# FPGA_IO.net
KiCad netlist of a schematic drawn in Altium Designer
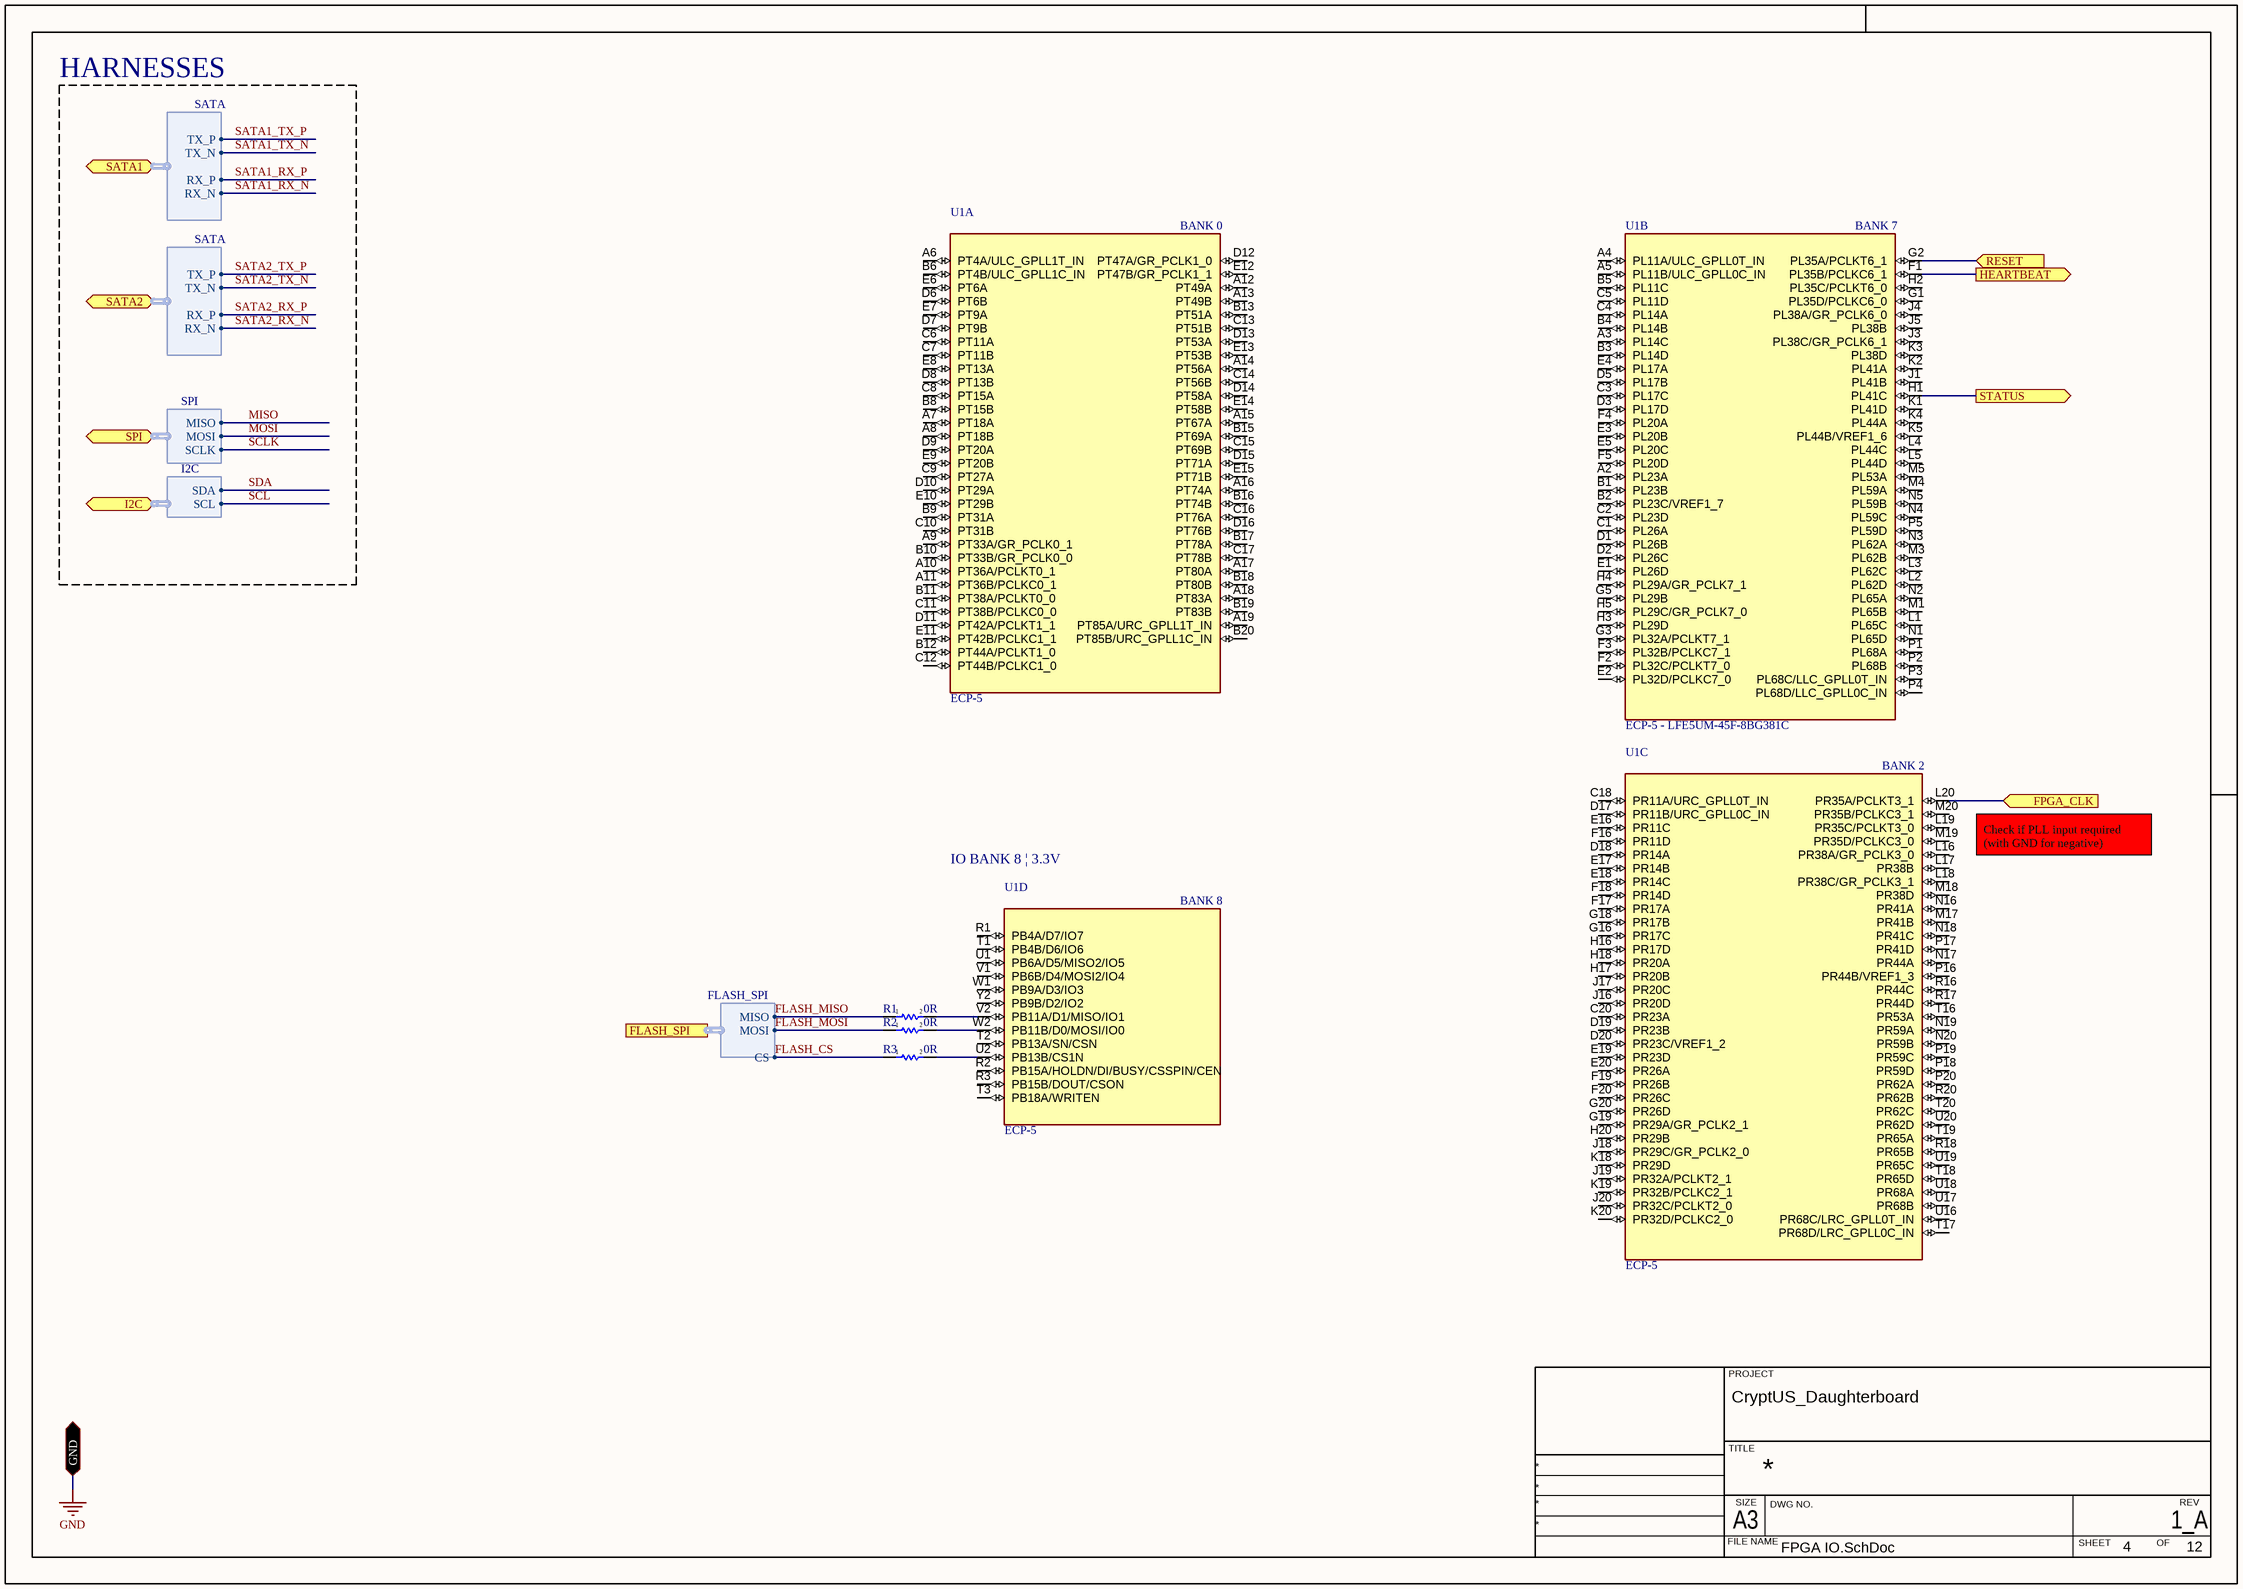
[diagram p0: FPGA IO.SchDoc]

(export (version "E")
  (design (tool "Eeschema 10.0.6"))
  (components
    (comp (ref "R1")
      (value "0R")
      (footprint "RES_0603")
      (description "Resistor")
      (fields (field (name "POWER") "1/8W") (field (name "TOLERANCE") "10%"))
      (libsource (lib "Symbols") (part "RESISTOR"))
    )
    (comp (ref "R2")
      (value "0R")
      (footprint "RES_0603")
      (description "Resistor")
      (fields (field (name "POWER") "1/8W") (field (name "TOLERANCE") "10%"))
      (libsource (lib "Symbols") (part "RESISTOR"))
    )
    (comp (ref "R3")
      (value "0R")
      (footprint "RES_0603")
      (description "Resistor")
      (fields (field (name "POWER") "1/8W") (field (name "TOLERANCE") "10%"))
      (libsource (lib "Symbols") (part "RESISTOR"))
    )
    (comp (ref "U1")
      (value "ECP-5")
      (footprint "CryptLib:CABGA-381")
      (description "IC FPGA 203 I/O 381CABGA")
      (fields (field (name "MFR") "Lattice Semiconductors"))
      (libsource (lib "CryptLib") (part "IC_LFE5UM-45F-8BG381C"))
    )
  )
  (nets
    (net (code "5") (name "/FLASH_CS") (class "Default")
      (node (ref "R3") (pin "1") (pinfunction "1_1") (pintype "passive"))
    )
    (net (code "6") (name "/FLASH_MISO") (class "Default")
      (node (ref "R1") (pin "1") (pinfunction "1_1") (pintype "passive"))
    )
    (net (code "7") (name "/FLASH_MOSI") (class "Default")
      (node (ref "R2") (pin "1") (pinfunction "1_1") (pintype "passive"))
    )
    (net (code "8") (name "/FPGA_CLK") (class "Default")
      (node (ref "U1") (pin "L20") (pinfunction "PR35A/PCLKT3_1_L20") (pintype "bidirectional"))
    )
    (net (code "9") (name "/HEARTBEAT") (class "Default")
      (node (ref "U1") (pin "F1") (pinfunction "PL35B/PCLKC6_1_F1") (pintype "bidirectional"))
    )
    (net (code "12") (name "/RESET") (class "Default")
      (node (ref "U1") (pin "G2") (pinfunction "PL35A/PCLKT6_1_G2") (pintype "bidirectional"))
    )
    (net (code "24") (name "/STATUS") (class "Default")
      (node (ref "U1") (pin "H1") (pinfunction "PL41C_H1") (pintype "bidirectional"))
    )
    (net (code "30") (name "Net-(U1D-PB11A{slash}D1{slash}MISO{slash}IO1)") (class "Default")
      (node (ref "R1") (pin "2") (pinfunction "2_2") (pintype "passive"))
      (node (ref "U1") (pin "V2") (pinfunction "PB11A/D1/MISO/IO1_V2") (pintype "bidirectional"))
    )
    (net (code "31") (name "Net-(U1D-PB11B{slash}D0{slash}MOSI{slash}IO0)") (class "Default")
      (node (ref "R2") (pin "2") (pinfunction "2_2") (pintype "passive"))
      (node (ref "U1") (pin "W2") (pinfunction "PB11B/D0/MOSI/IO0_W2") (pintype "bidirectional"))
    )
    (net (code "32") (name "Net-(U1D-PB13B{slash}CS1N)") (class "Default")
      (node (ref "R3") (pin "2") (pinfunction "2_2") (pintype "passive"))
      (node (ref "U1") (pin "U2") (pinfunction "PB13B/CS1N_U2") (pintype "bidirectional"))
    )
    (net (code "33") (name "unconnected-(U1A-PT4A{slash}ULC_GPLL1T_IN-PadA6)") (class "Default")
      (node (ref "U1") (pin "A6") (pinfunction "PT4A/ULC_GPLL1T_IN_A6") (pintype "bidirectional"))
    )
    (net (code "34") (name "unconnected-(U1A-PT4B{slash}ULC_GPLL1C_IN-PadB6)") (class "Default")
      (node (ref "U1") (pin "B6") (pinfunction "PT4B/ULC_GPLL1C_IN_B6") (pintype "bidirectional"))
    )
    (net (code "35") (name "unconnected-(U1A-PT6A-PadE6)") (class "Default")
      (node (ref "U1") (pin "E6") (pinfunction "PT6A_E6") (pintype "bidirectional"))
    )
    (net (code "36") (name "unconnected-(U1A-PT6B-PadD6)") (class "Default")
      (node (ref "U1") (pin "D6") (pinfunction "PT6B_D6") (pintype "bidirectional"))
    )
    (net (code "37") (name "unconnected-(U1A-PT9A-PadE7)") (class "Default")
      (node (ref "U1") (pin "E7") (pinfunction "PT9A_E7") (pintype "bidirectional"))
    )
    (net (code "38") (name "unconnected-(U1A-PT9B-PadD7)") (class "Default")
      (node (ref "U1") (pin "D7") (pinfunction "PT9B_D7") (pintype "bidirectional"))
    )
    (net (code "39") (name "unconnected-(U1A-PT11A-PadC6)") (class "Default")
      (node (ref "U1") (pin "C6") (pinfunction "PT11A_C6") (pintype "bidirectional"))
    )
    (net (code "40") (name "unconnected-(U1A-PT11B-PadC7)") (class "Default")
      (node (ref "U1") (pin "C7") (pinfunction "PT11B_C7") (pintype "bidirectional"))
    )
    (net (code "41") (name "unconnected-(U1A-PT13A-PadE8)") (class "Default")
      (node (ref "U1") (pin "E8") (pinfunction "PT13A_E8") (pintype "bidirectional"))
    )
    (net (code "42") (name "unconnected-(U1A-PT13B-PadD8)") (class "Default")
      (node (ref "U1") (pin "D8") (pinfunction "PT13B_D8") (pintype "bidirectional"))
    )
    (net (code "43") (name "unconnected-(U1A-PT15A-PadC8)") (class "Default")
      (node (ref "U1") (pin "C8") (pinfunction "PT15A_C8") (pintype "bidirectional"))
    )
    (net (code "44") (name "unconnected-(U1A-PT15B-PadB8)") (class "Default")
      (node (ref "U1") (pin "B8") (pinfunction "PT15B_B8") (pintype "bidirectional"))
    )
    (net (code "45") (name "unconnected-(U1A-PT18A-PadA7)") (class "Default")
      (node (ref "U1") (pin "A7") (pinfunction "PT18A_A7") (pintype "bidirectional"))
    )
    (net (code "46") (name "unconnected-(U1A-PT18B-PadA8)") (class "Default")
      (node (ref "U1") (pin "A8") (pinfunction "PT18B_A8") (pintype "bidirectional"))
    )
    (net (code "47") (name "unconnected-(U1A-PT20A-PadD9)") (class "Default")
      (node (ref "U1") (pin "D9") (pinfunction "PT20A_D9") (pintype "bidirectional"))
    )
    (net (code "48") (name "unconnected-(U1A-PT20B-PadE9)") (class "Default")
      (node (ref "U1") (pin "E9") (pinfunction "PT20B_E9") (pintype "bidirectional"))
    )
    (net (code "49") (name "unconnected-(U1A-PT27A-PadC9)") (class "Default")
      (node (ref "U1") (pin "C9") (pinfunction "PT27A_C9") (pintype "bidirectional"))
    )
    (net (code "50") (name "unconnected-(U1A-PT29A-PadD10)") (class "Default")
      (node (ref "U1") (pin "D10") (pinfunction "PT29A_D10") (pintype "bidirectional"))
    )
    (net (code "51") (name "unconnected-(U1A-PT29B-PadE10)") (class "Default")
      (node (ref "U1") (pin "E10") (pinfunction "PT29B_E10") (pintype "bidirectional"))
    )
    (net (code "52") (name "unconnected-(U1A-PT31A-PadB9)") (class "Default")
      (node (ref "U1") (pin "B9") (pinfunction "PT31A_B9") (pintype "bidirectional"))
    )
    (net (code "53") (name "unconnected-(U1A-PT31B-PadC10)") (class "Default")
      (node (ref "U1") (pin "C10") (pinfunction "PT31B_C10") (pintype "bidirectional"))
    )
    (net (code "54") (name "unconnected-(U1A-PT33A{slash}GR_PCLK0_1-PadA9)") (class "Default")
      (node (ref "U1") (pin "A9") (pinfunction "PT33A/GR_PCLK0_1_A9") (pintype "bidirectional"))
    )
    (net (code "55") (name "unconnected-(U1A-PT33B{slash}GR_PCLK0_0-PadB10)") (class "Default")
      (node (ref "U1") (pin "B10") (pinfunction "PT33B/GR_PCLK0_0_B10") (pintype "bidirectional"))
    )
    (net (code "56") (name "unconnected-(U1A-PT36A{slash}PCLKT0_1-PadA10)") (class "Default")
      (node (ref "U1") (pin "A10") (pinfunction "PT36A/PCLKT0_1_A10") (pintype "bidirectional"))
    )
    (net (code "57") (name "unconnected-(U1A-PT36B{slash}PCLKC0_1-PadA11)") (class "Default")
      (node (ref "U1") (pin "A11") (pinfunction "PT36B/PCLKC0_1_A11") (pintype "bidirectional"))
    )
    (net (code "58") (name "unconnected-(U1A-PT38A{slash}PCLKT0_0-PadB11)") (class "Default")
      (node (ref "U1") (pin "B11") (pinfunction "PT38A/PCLKT0_0_B11") (pintype "bidirectional"))
    )
    (net (code "59") (name "unconnected-(U1A-PT38B{slash}PCLKC0_0-PadC11)") (class "Default")
      (node (ref "U1") (pin "C11") (pinfunction "PT38B/PCLKC0_0_C11") (pintype "bidirectional"))
    )
    (net (code "60") (name "unconnected-(U1A-PT42A{slash}PCLKT1_1-PadD11)") (class "Default")
      (node (ref "U1") (pin "D11") (pinfunction "PT42A/PCLKT1_1_D11") (pintype "bidirectional"))
    )
    (net (code "61") (name "unconnected-(U1A-PT42B{slash}PCLKC1_1-PadE11)") (class "Default")
      (node (ref "U1") (pin "E11") (pinfunction "PT42B/PCLKC1_1_E11") (pintype "bidirectional"))
    )
    (net (code "62") (name "unconnected-(U1A-PT44A{slash}PCLKT1_0-PadB12)") (class "Default")
      (node (ref "U1") (pin "B12") (pinfunction "PT44A/PCLKT1_0_B12") (pintype "bidirectional"))
    )
    (net (code "63") (name "unconnected-(U1A-PT44B{slash}PCLKC1_0-PadC12)") (class "Default")
      (node (ref "U1") (pin "C12") (pinfunction "PT44B/PCLKC1_0_C12") (pintype "bidirectional"))
    )
    (net (code "64") (name "unconnected-(U1A-PT47A{slash}GR_PCLK1_0-PadD12)") (class "Default")
      (node (ref "U1") (pin "D12") (pinfunction "PT47A/GR_PCLK1_0_D12") (pintype "bidirectional"))
    )
    (net (code "65") (name "unconnected-(U1A-PT47B{slash}GR_PCLK1_1-PadE12)") (class "Default")
      (node (ref "U1") (pin "E12") (pinfunction "PT47B/GR_PCLK1_1_E12") (pintype "bidirectional"))
    )
    (net (code "66") (name "unconnected-(U1A-PT49A-PadA12)") (class "Default")
      (node (ref "U1") (pin "A12") (pinfunction "PT49A_A12") (pintype "bidirectional"))
    )
    (net (code "67") (name "unconnected-(U1A-PT49B-PadA13)") (class "Default")
      (node (ref "U1") (pin "A13") (pinfunction "PT49B_A13") (pintype "bidirectional"))
    )
    (net (code "68") (name "unconnected-(U1A-PT51A-PadB13)") (class "Default")
      (node (ref "U1") (pin "B13") (pinfunction "PT51A_B13") (pintype "bidirectional"))
    )
    (net (code "69") (name "unconnected-(U1A-PT51B-PadC13)") (class "Default")
      (node (ref "U1") (pin "C13") (pinfunction "PT51B_C13") (pintype "bidirectional"))
    )
    (net (code "70") (name "unconnected-(U1A-PT53A-PadD13)") (class "Default")
      (node (ref "U1") (pin "D13") (pinfunction "PT53A_D13") (pintype "bidirectional"))
    )
    (net (code "71") (name "unconnected-(U1A-PT53B-PadE13)") (class "Default")
      (node (ref "U1") (pin "E13") (pinfunction "PT53B_E13") (pintype "bidirectional"))
    )
    (net (code "72") (name "unconnected-(U1A-PT56A-PadA14)") (class "Default")
      (node (ref "U1") (pin "A14") (pinfunction "PT56A_A14") (pintype "bidirectional"))
    )
    (net (code "73") (name "unconnected-(U1A-PT56B-PadC14)") (class "Default")
      (node (ref "U1") (pin "C14") (pinfunction "PT56B_C14") (pintype "bidirectional"))
    )
    (net (code "74") (name "unconnected-(U1A-PT58A-PadD14)") (class "Default")
      (node (ref "U1") (pin "D14") (pinfunction "PT58A_D14") (pintype "bidirectional"))
    )
    (net (code "75") (name "unconnected-(U1A-PT58B-PadE14)") (class "Default")
      (node (ref "U1") (pin "E14") (pinfunction "PT58B_E14") (pintype "bidirectional"))
    )
    (net (code "76") (name "unconnected-(U1A-PT67A-PadA15)") (class "Default")
      (node (ref "U1") (pin "A15") (pinfunction "PT67A_A15") (pintype "bidirectional"))
    )
    (net (code "77") (name "unconnected-(U1A-PT69A-PadB15)") (class "Default")
      (node (ref "U1") (pin "B15") (pinfunction "PT69A_B15") (pintype "bidirectional"))
    )
    (net (code "78") (name "unconnected-(U1A-PT69B-PadC15)") (class "Default")
      (node (ref "U1") (pin "C15") (pinfunction "PT69B_C15") (pintype "bidirectional"))
    )
    (net (code "79") (name "unconnected-(U1A-PT71A-PadD15)") (class "Default")
      (node (ref "U1") (pin "D15") (pinfunction "PT71A_D15") (pintype "bidirectional"))
    )
    (net (code "80") (name "unconnected-(U1A-PT71B-PadE15)") (class "Default")
      (node (ref "U1") (pin "E15") (pinfunction "PT71B_E15") (pintype "bidirectional"))
    )
    (net (code "81") (name "unconnected-(U1A-PT74A-PadA16)") (class "Default")
      (node (ref "U1") (pin "A16") (pinfunction "PT74A_A16") (pintype "bidirectional"))
    )
    (net (code "82") (name "unconnected-(U1A-PT74B-PadB16)") (class "Default")
      (node (ref "U1") (pin "B16") (pinfunction "PT74B_B16") (pintype "bidirectional"))
    )
    (net (code "83") (name "unconnected-(U1A-PT76A-PadC16)") (class "Default")
      (node (ref "U1") (pin "C16") (pinfunction "PT76A_C16") (pintype "bidirectional"))
    )
    (net (code "84") (name "unconnected-(U1A-PT76B-PadD16)") (class "Default")
      (node (ref "U1") (pin "D16") (pinfunction "PT76B_D16") (pintype "bidirectional"))
    )
    (net (code "85") (name "unconnected-(U1A-PT78A-PadB17)") (class "Default")
      (node (ref "U1") (pin "B17") (pinfunction "PT78A_B17") (pintype "bidirectional"))
    )
    (net (code "86") (name "unconnected-(U1A-PT78B-PadC17)") (class "Default")
      (node (ref "U1") (pin "C17") (pinfunction "PT78B_C17") (pintype "bidirectional"))
    )
    (net (code "87") (name "unconnected-(U1A-PT80A-PadA17)") (class "Default")
      (node (ref "U1") (pin "A17") (pinfunction "PT80A_A17") (pintype "bidirectional"))
    )
    (net (code "88") (name "unconnected-(U1A-PT80B-PadB18)") (class "Default")
      (node (ref "U1") (pin "B18") (pinfunction "PT80B_B18") (pintype "bidirectional"))
    )
    (net (code "89") (name "unconnected-(U1A-PT83A-PadA18)") (class "Default")
      (node (ref "U1") (pin "A18") (pinfunction "PT83A_A18") (pintype "bidirectional"))
    )
    (net (code "90") (name "unconnected-(U1A-PT83B-PadB19)") (class "Default")
      (node (ref "U1") (pin "B19") (pinfunction "PT83B_B19") (pintype "bidirectional"))
    )
    (net (code "91") (name "unconnected-(U1A-PT85A{slash}URC_GPLL1T_IN-PadA19)") (class "Default")
      (node (ref "U1") (pin "A19") (pinfunction "PT85A/URC_GPLL1T_IN_A19") (pintype "bidirectional"))
    )
    (net (code "92") (name "unconnected-(U1A-PT85B{slash}URC_GPLL1C_IN-PadB20)") (class "Default")
      (node (ref "U1") (pin "B20") (pinfunction "PT85B/URC_GPLL1C_IN_B20") (pintype "bidirectional"))
    )
    (net (code "93") (name "unconnected-(U1B-PL11A{slash}ULC_GPLL0T_IN-PadA4)") (class "Default")
      (node (ref "U1") (pin "A4") (pinfunction "PL11A/ULC_GPLL0T_IN_A4") (pintype "bidirectional"))
    )
    (net (code "94") (name "unconnected-(U1B-PL11B{slash}ULC_GPLL0C_IN-PadA5)") (class "Default")
      (node (ref "U1") (pin "A5") (pinfunction "PL11B/ULC_GPLL0C_IN_A5") (pintype "bidirectional"))
    )
    (net (code "95") (name "unconnected-(U1B-PL11C-PadB5)") (class "Default")
      (node (ref "U1") (pin "B5") (pinfunction "PL11C_B5") (pintype "bidirectional"))
    )
    (net (code "96") (name "unconnected-(U1B-PL11D-PadC5)") (class "Default")
      (node (ref "U1") (pin "C5") (pinfunction "PL11D_C5") (pintype "bidirectional"))
    )
    (net (code "97") (name "unconnected-(U1B-PL14A-PadC4)") (class "Default")
      (node (ref "U1") (pin "C4") (pinfunction "PL14A_C4") (pintype "bidirectional"))
    )
    (net (code "98") (name "unconnected-(U1B-PL14B-PadB4)") (class "Default")
      (node (ref "U1") (pin "B4") (pinfunction "PL14B_B4") (pintype "bidirectional"))
    )
    (net (code "99") (name "unconnected-(U1B-PL14C-PadA3)") (class "Default")
      (node (ref "U1") (pin "A3") (pinfunction "PL14C_A3") (pintype "bidirectional"))
    )
    (net (code "100") (name "unconnected-(U1B-PL14D-PadB3)") (class "Default")
      (node (ref "U1") (pin "B3") (pinfunction "PL14D_B3") (pintype "bidirectional"))
    )
    (net (code "101") (name "unconnected-(U1B-PL17A-PadE4)") (class "Default")
      (node (ref "U1") (pin "E4") (pinfunction "PL17A_E4") (pintype "bidirectional"))
    )
    (net (code "102") (name "unconnected-(U1B-PL17B-PadD5)") (class "Default")
      (node (ref "U1") (pin "D5") (pinfunction "PL17B_D5") (pintype "bidirectional"))
    )
    (net (code "103") (name "unconnected-(U1B-PL17C-PadC3)") (class "Default")
      (node (ref "U1") (pin "C3") (pinfunction "PL17C_C3") (pintype "bidirectional"))
    )
    (net (code "104") (name "unconnected-(U1B-PL17D-PadD3)") (class "Default")
      (node (ref "U1") (pin "D3") (pinfunction "PL17D_D3") (pintype "bidirectional"))
    )
    (net (code "105") (name "unconnected-(U1B-PL20A-PadF4)") (class "Default")
      (node (ref "U1") (pin "F4") (pinfunction "PL20A_F4") (pintype "bidirectional"))
    )
    (net (code "106") (name "unconnected-(U1B-PL20B-PadE3)") (class "Default")
      (node (ref "U1") (pin "E3") (pinfunction "PL20B_E3") (pintype "bidirectional"))
    )
    (net (code "107") (name "unconnected-(U1B-PL20C-PadE5)") (class "Default")
      (node (ref "U1") (pin "E5") (pinfunction "PL20C_E5") (pintype "bidirectional"))
    )
    (net (code "108") (name "unconnected-(U1B-PL20D-PadF5)") (class "Default")
      (node (ref "U1") (pin "F5") (pinfunction "PL20D_F5") (pintype "bidirectional"))
    )
    (net (code "109") (name "unconnected-(U1B-PL23A-PadA2)") (class "Default")
      (node (ref "U1") (pin "A2") (pinfunction "PL23A_A2") (pintype "bidirectional"))
    )
    (net (code "110") (name "unconnected-(U1B-PL23B-PadB1)") (class "Default")
      (node (ref "U1") (pin "B1") (pinfunction "PL23B_B1") (pintype "bidirectional"))
    )
    (net (code "111") (name "unconnected-(U1B-PL23C{slash}VREF1_7-PadB2)") (class "Default")
      (node (ref "U1") (pin "B2") (pinfunction "PL23C/VREF1_7_B2") (pintype "bidirectional"))
    )
    (net (code "112") (name "unconnected-(U1B-PL23D-PadC2)") (class "Default")
      (node (ref "U1") (pin "C2") (pinfunction "PL23D_C2") (pintype "bidirectional"))
    )
    (net (code "113") (name "unconnected-(U1B-PL26A-PadC1)") (class "Default")
      (node (ref "U1") (pin "C1") (pinfunction "PL26A_C1") (pintype "bidirectional"))
    )
    (net (code "114") (name "unconnected-(U1B-PL26B-PadD1)") (class "Default")
      (node (ref "U1") (pin "D1") (pinfunction "PL26B_D1") (pintype "bidirectional"))
    )
    (net (code "115") (name "unconnected-(U1B-PL26C-PadD2)") (class "Default")
      (node (ref "U1") (pin "D2") (pinfunction "PL26C_D2") (pintype "bidirectional"))
    )
    (net (code "116") (name "unconnected-(U1B-PL26D-PadE1)") (class "Default")
      (node (ref "U1") (pin "E1") (pinfunction "PL26D_E1") (pintype "bidirectional"))
    )
    (net (code "117") (name "unconnected-(U1B-PL29A{slash}GR_PCLK7_1-PadH4)") (class "Default")
      (node (ref "U1") (pin "H4") (pinfunction "PL29A/GR_PCLK7_1_H4") (pintype "bidirectional"))
    )
    (net (code "118") (name "unconnected-(U1B-PL29B-PadG5)") (class "Default")
      (node (ref "U1") (pin "G5") (pinfunction "PL29B_G5") (pintype "bidirectional"))
    )
    (net (code "119") (name "unconnected-(U1B-PL29C{slash}GR_PCLK7_0-PadH5)") (class "Default")
      (node (ref "U1") (pin "H5") (pinfunction "PL29C/GR_PCLK7_0_H5") (pintype "bidirectional"))
    )
    (net (code "120") (name "unconnected-(U1B-PL29D-PadH3)") (class "Default")
      (node (ref "U1") (pin "H3") (pinfunction "PL29D_H3") (pintype "bidirectional"))
    )
    (net (code "121") (name "unconnected-(U1B-PL32A{slash}PCLKT7_1-PadG3)") (class "Default")
      (node (ref "U1") (pin "G3") (pinfunction "PL32A/PCLKT7_1_G3") (pintype "bidirectional"))
    )
    (net (code "122") (name "unconnected-(U1B-PL32B{slash}PCLKC7_1-PadF3)") (class "Default")
      (node (ref "U1") (pin "F3") (pinfunction "PL32B/PCLKC7_1_F3") (pintype "bidirectional"))
    )
    (net (code "123") (name "unconnected-(U1B-PL32C{slash}PCLKT7_0-PadF2)") (class "Default")
      (node (ref "U1") (pin "F2") (pinfunction "PL32C/PCLKT7_0_F2") (pintype "bidirectional"))
    )
    (net (code "124") (name "unconnected-(U1B-PL32D{slash}PCLKC7_0-PadE2)") (class "Default")
      (node (ref "U1") (pin "E2") (pinfunction "PL32D/PCLKC7_0_E2") (pintype "bidirectional"))
    )
    (net (code "125") (name "unconnected-(U1B-PL35C{slash}PCLKT6_0-PadH2)") (class "Default")
      (node (ref "U1") (pin "H2") (pinfunction "PL35C/PCLKT6_0_H2") (pintype "bidirectional"))
    )
    (net (code "126") (name "unconnected-(U1B-PL35D{slash}PCLKC6_0-PadG1)") (class "Default")
      (node (ref "U1") (pin "G1") (pinfunction "PL35D/PCLKC6_0_G1") (pintype "bidirectional"))
    )
    (net (code "127") (name "unconnected-(U1B-PL38A{slash}GR_PCLK6_0-PadJ4)") (class "Default")
      (node (ref "U1") (pin "J4") (pinfunction "PL38A/GR_PCLK6_0_J4") (pintype "bidirectional"))
    )
    (net (code "128") (name "unconnected-(U1B-PL38B-PadJ5)") (class "Default")
      (node (ref "U1") (pin "J5") (pinfunction "PL38B_J5") (pintype "bidirectional"))
    )
    (net (code "129") (name "unconnected-(U1B-PL38C{slash}GR_PCLK6_1-PadJ3)") (class "Default")
      (node (ref "U1") (pin "J3") (pinfunction "PL38C/GR_PCLK6_1_J3") (pintype "bidirectional"))
    )
    (net (code "130") (name "unconnected-(U1B-PL38D-PadK3)") (class "Default")
      (node (ref "U1") (pin "K3") (pinfunction "PL38D_K3") (pintype "bidirectional"))
    )
    (net (code "131") (name "unconnected-(U1B-PL41A-PadK2)") (class "Default")
      (node (ref "U1") (pin "K2") (pinfunction "PL41A_K2") (pintype "bidirectional"))
    )
    (net (code "132") (name "unconnected-(U1B-PL41B-PadJ1)") (class "Default")
      (node (ref "U1") (pin "J1") (pinfunction "PL41B_J1") (pintype "bidirectional"))
    )
    (net (code "133") (name "unconnected-(U1B-PL41D-PadK1)") (class "Default")
      (node (ref "U1") (pin "K1") (pinfunction "PL41D_K1") (pintype "bidirectional"))
    )
    (net (code "134") (name "unconnected-(U1B-PL44A-PadK4)") (class "Default")
      (node (ref "U1") (pin "K4") (pinfunction "PL44A_K4") (pintype "bidirectional"))
    )
    (net (code "135") (name "unconnected-(U1B-PL44B{slash}VREF1_6-PadK5)") (class "Default")
      (node (ref "U1") (pin "K5") (pinfunction "PL44B/VREF1_6_K5") (pintype "bidirectional"))
    )
    (net (code "136") (name "unconnected-(U1B-PL44C-PadL4)") (class "Default")
      (node (ref "U1") (pin "L4") (pinfunction "PL44C_L4") (pintype "bidirectional"))
    )
    (net (code "137") (name "unconnected-(U1B-PL44D-PadL5)") (class "Default")
      (node (ref "U1") (pin "L5") (pinfunction "PL44D_L5") (pintype "bidirectional"))
    )
    (net (code "138") (name "unconnected-(U1B-PL53A-PadM5)") (class "Default")
      (node (ref "U1") (pin "M5") (pinfunction "PL53A_M5") (pintype "bidirectional"))
    )
    (net (code "139") (name "unconnected-(U1B-PL59A-PadM4)") (class "Default")
      (node (ref "U1") (pin "M4") (pinfunction "PL59A_M4") (pintype "bidirectional"))
    )
    (net (code "140") (name "unconnected-(U1B-PL59B-PadN5)") (class "Default")
      (node (ref "U1") (pin "N5") (pinfunction "PL59B_N5") (pintype "bidirectional"))
    )
    (net (code "141") (name "unconnected-(U1B-PL59C-PadN4)") (class "Default")
      (node (ref "U1") (pin "N4") (pinfunction "PL59C_N4") (pintype "bidirectional"))
    )
    (net (code "142") (name "unconnected-(U1B-PL59D-PadP5)") (class "Default")
      (node (ref "U1") (pin "P5") (pinfunction "PL59D_P5") (pintype "bidirectional"))
    )
    (net (code "143") (name "unconnected-(U1B-PL62A-PadN3)") (class "Default")
      (node (ref "U1") (pin "N3") (pinfunction "PL62A_N3") (pintype "bidirectional"))
    )
    (net (code "144") (name "unconnected-(U1B-PL62B-PadM3)") (class "Default")
      (node (ref "U1") (pin "M3") (pinfunction "PL62B_M3") (pintype "bidirectional"))
    )
    (net (code "145") (name "unconnected-(U1B-PL62C-PadL3)") (class "Default")
      (node (ref "U1") (pin "L3") (pinfunction "PL62C_L3") (pintype "bidirectional"))
    )
    (net (code "146") (name "unconnected-(U1B-PL62D-PadL2)") (class "Default")
      (node (ref "U1") (pin "L2") (pinfunction "PL62D_L2") (pintype "bidirectional"))
    )
    (net (code "147") (name "unconnected-(U1B-PL65A-PadN2)") (class "Default")
      (node (ref "U1") (pin "N2") (pinfunction "PL65A_N2") (pintype "bidirectional"))
    )
    (net (code "148") (name "unconnected-(U1B-PL65B-PadM1)") (class "Default")
      (node (ref "U1") (pin "M1") (pinfunction "PL65B_M1") (pintype "bidirectional"))
    )
    (net (code "149") (name "unconnected-(U1B-PL65C-PadL1)") (class "Default")
      (node (ref "U1") (pin "L1") (pinfunction "PL65C_L1") (pintype "bidirectional"))
    )
    (net (code "150") (name "unconnected-(U1B-PL65D-PadN1)") (class "Default")
      (node (ref "U1") (pin "N1") (pinfunction "PL65D_N1") (pintype "bidirectional"))
    )
    (net (code "151") (name "unconnected-(U1B-PL68A-PadP1)") (class "Default")
      (node (ref "U1") (pin "P1") (pinfunction "PL68A_P1") (pintype "bidirectional"))
    )
    (net (code "152") (name "unconnected-(U1B-PL68B-PadP2)") (class "Default")
      (node (ref "U1") (pin "P2") (pinfunction "PL68B_P2") (pintype "bidirectional"))
    )
    (net (code "153") (name "unconnected-(U1B-PL68C{slash}LLC_GPLL0T_IN-PadP3)") (class "Default")
      (node (ref "U1") (pin "P3") (pinfunction "PL68C/LLC_GPLL0T_IN_P3") (pintype "bidirectional"))
    )
    (net (code "154") (name "unconnected-(U1B-PL68D{slash}LLC_GPLL0C_IN-PadP4)") (class "Default")
      (node (ref "U1") (pin "P4") (pinfunction "PL68D/LLC_GPLL0C_IN_P4") (pintype "bidirectional"))
    )
    (net (code "155") (name "unconnected-(U1C-PR11A{slash}URC_GPLL0T_IN-PadC18)") (class "Default")
      (node (ref "U1") (pin "C18") (pinfunction "PR11A/URC_GPLL0T_IN_C18") (pintype "bidirectional"))
    )
    (net (code "156") (name "unconnected-(U1C-PR11B{slash}URC_GPLL0C_IN-PadD17)") (class "Default")
      (node (ref "U1") (pin "D17") (pinfunction "PR11B/URC_GPLL0C_IN_D17") (pintype "bidirectional"))
    )
    (net (code "157") (name "unconnected-(U1C-PR11C-PadE16)") (class "Default")
      (node (ref "U1") (pin "E16") (pinfunction "PR11C_E16") (pintype "bidirectional"))
    )
    (net (code "158") (name "unconnected-(U1C-PR11D-PadF16)") (class "Default")
      (node (ref "U1") (pin "F16") (pinfunction "PR11D_F16") (pintype "bidirectional"))
    )
    (net (code "159") (name "unconnected-(U1C-PR14A-PadD18)") (class "Default")
      (node (ref "U1") (pin "D18") (pinfunction "PR14A_D18") (pintype "bidirectional"))
    )
    (net (code "160") (name "unconnected-(U1C-PR14B-PadE17)") (class "Default")
      (node (ref "U1") (pin "E17") (pinfunction "PR14B_E17") (pintype "bidirectional"))
    )
    (net (code "161") (name "unconnected-(U1C-PR14C-PadE18)") (class "Default")
      (node (ref "U1") (pin "E18") (pinfunction "PR14C_E18") (pintype "bidirectional"))
    )
    (net (code "162") (name "unconnected-(U1C-PR14D-PadF18)") (class "Default")
      (node (ref "U1") (pin "F18") (pinfunction "PR14D_F18") (pintype "bidirectional"))
    )
    (net (code "163") (name "unconnected-(U1C-PR17A-PadF17)") (class "Default")
      (node (ref "U1") (pin "F17") (pinfunction "PR17A_F17") (pintype "bidirectional"))
    )
    (net (code "164") (name "unconnected-(U1C-PR17B-PadG18)") (class "Default")
      (node (ref "U1") (pin "G18") (pinfunction "PR17B_G18") (pintype "bidirectional"))
    )
    (net (code "165") (name "unconnected-(U1C-PR17C-PadG16)") (class "Default")
      (node (ref "U1") (pin "G16") (pinfunction "PR17C_G16") (pintype "bidirectional"))
    )
    (net (code "166") (name "unconnected-(U1C-PR17D-PadH16)") (class "Default")
      (node (ref "U1") (pin "H16") (pinfunction "PR17D_H16") (pintype "bidirectional"))
    )
    (net (code "167") (name "unconnected-(U1C-PR20A-PadH18)") (class "Default")
      (node (ref "U1") (pin "H18") (pinfunction "PR20A_H18") (pintype "bidirectional"))
    )
    (net (code "168") (name "unconnected-(U1C-PR20B-PadH17)") (class "Default")
      (node (ref "U1") (pin "H17") (pinfunction "PR20B_H17") (pintype "bidirectional"))
    )
    (net (code "169") (name "unconnected-(U1C-PR20C-PadJ17)") (class "Default")
      (node (ref "U1") (pin "J17") (pinfunction "PR20C_J17") (pintype "bidirectional"))
    )
    (net (code "170") (name "unconnected-(U1C-PR20D-PadJ16)") (class "Default")
      (node (ref "U1") (pin "J16") (pinfunction "PR20D_J16") (pintype "bidirectional"))
    )
    (net (code "171") (name "unconnected-(U1C-PR23A-PadC20)") (class "Default")
      (node (ref "U1") (pin "C20") (pinfunction "PR23A_C20") (pintype "bidirectional"))
    )
    (net (code "172") (name "unconnected-(U1C-PR23B-PadD19)") (class "Default")
      (node (ref "U1") (pin "D19") (pinfunction "PR23B_D19") (pintype "bidirectional"))
    )
    (net (code "173") (name "unconnected-(U1C-PR23C{slash}VREF1_2-PadD20)") (class "Default")
      (node (ref "U1") (pin "D20") (pinfunction "PR23C/VREF1_2_D20") (pintype "bidirectional"))
    )
    (net (code "174") (name "unconnected-(U1C-PR23D-PadE19)") (class "Default")
      (node (ref "U1") (pin "E19") (pinfunction "PR23D_E19") (pintype "bidirectional"))
    )
    (net (code "175") (name "unconnected-(U1C-PR26A-PadE20)") (class "Default")
      (node (ref "U1") (pin "E20") (pinfunction "PR26A_E20") (pintype "bidirectional"))
    )
    (net (code "176") (name "unconnected-(U1C-PR26B-PadF19)") (class "Default")
      (node (ref "U1") (pin "F19") (pinfunction "PR26B_F19") (pintype "bidirectional"))
    )
    (net (code "177") (name "unconnected-(U1C-PR26C-PadF20)") (class "Default")
      (node (ref "U1") (pin "F20") (pinfunction "PR26C_F20") (pintype "bidirectional"))
    )
    (net (code "178") (name "unconnected-(U1C-PR26D-PadG20)") (class "Default")
      (node (ref "U1") (pin "G20") (pinfunction "PR26D_G20") (pintype "bidirectional"))
    )
    (net (code "179") (name "unconnected-(U1C-PR29A{slash}GR_PCLK2_1-PadG19)") (class "Default")
      (node (ref "U1") (pin "G19") (pinfunction "PR29A/GR_PCLK2_1_G19") (pintype "bidirectional"))
    )
    (net (code "180") (name "unconnected-(U1C-PR29B-PadH20)") (class "Default")
      (node (ref "U1") (pin "H20") (pinfunction "PR29B_H20") (pintype "bidirectional"))
    )
    (net (code "181") (name "unconnected-(U1C-PR29C{slash}GR_PCLK2_0-PadJ18)") (class "Default")
      (node (ref "U1") (pin "J18") (pinfunction "PR29C/GR_PCLK2_0_J18") (pintype "bidirectional"))
    )
    (net (code "182") (name "unconnected-(U1C-PR29D-PadK18)") (class "Default")
      (node (ref "U1") (pin "K18") (pinfunction "PR29D_K18") (pintype "bidirectional"))
    )
    (net (code "183") (name "unconnected-(U1C-PR32A{slash}PCLKT2_1-PadJ19)") (class "Default")
      (node (ref "U1") (pin "J19") (pinfunction "PR32A/PCLKT2_1_J19") (pintype "bidirectional"))
    )
    (net (code "184") (name "unconnected-(U1C-PR32B{slash}PCLKC2_1-PadK19)") (class "Default")
      (node (ref "U1") (pin "K19") (pinfunction "PR32B/PCLKC2_1_K19") (pintype "bidirectional"))
    )
    (net (code "185") (name "unconnected-(U1C-PR32C{slash}PCLKT2_0-PadJ20)") (class "Default")
      (node (ref "U1") (pin "J20") (pinfunction "PR32C/PCLKT2_0_J20") (pintype "bidirectional"))
    )
    (net (code "186") (name "unconnected-(U1C-PR32D{slash}PCLKC2_0-PadK20)") (class "Default")
      (node (ref "U1") (pin "K20") (pinfunction "PR32D/PCLKC2_0_K20") (pintype "bidirectional"))
    )
    (net (code "187") (name "unconnected-(U1C-PR35B{slash}PCLKC3_1-PadM20)") (class "Default")
      (node (ref "U1") (pin "M20") (pinfunction "PR35B/PCLKC3_1_M20") (pintype "bidirectional"))
    )
    (net (code "188") (name "unconnected-(U1C-PR35C{slash}PCLKT3_0-PadL19)") (class "Default")
      (node (ref "U1") (pin "L19") (pinfunction "PR35C/PCLKT3_0_L19") (pintype "bidirectional"))
    )
    (net (code "189") (name "unconnected-(U1C-PR35D{slash}PCLKC3_0-PadM19)") (class "Default")
      (node (ref "U1") (pin "M19") (pinfunction "PR35D/PCLKC3_0_M19") (pintype "bidirectional"))
    )
    (net (code "190") (name "unconnected-(U1C-PR38A{slash}GR_PCLK3_0-PadL16)") (class "Default")
      (node (ref "U1") (pin "L16") (pinfunction "PR38A/GR_PCLK3_0_L16") (pintype "bidirectional"))
    )
    (net (code "191") (name "unconnected-(U1C-PR38B-PadL17)") (class "Default")
      (node (ref "U1") (pin "L17") (pinfunction "PR38B_L17") (pintype "bidirectional"))
    )
    (net (code "192") (name "unconnected-(U1C-PR38C{slash}GR_PCLK3_1-PadL18)") (class "Default")
      (node (ref "U1") (pin "L18") (pinfunction "PR38C/GR_PCLK3_1_L18") (pintype "bidirectional"))
    )
    (net (code "193") (name "unconnected-(U1C-PR38D-PadM18)") (class "Default")
      (node (ref "U1") (pin "M18") (pinfunction "PR38D_M18") (pintype "bidirectional"))
    )
    (net (code "194") (name "unconnected-(U1C-PR41A-PadN16)") (class "Default")
      (node (ref "U1") (pin "N16") (pinfunction "PR41A_N16") (pintype "bidirectional"))
    )
    (net (code "195") (name "unconnected-(U1C-PR41B-PadM17)") (class "Default")
      (node (ref "U1") (pin "M17") (pinfunction "PR41B_M17") (pintype "bidirectional"))
    )
    (net (code "196") (name "unconnected-(U1C-PR41C-PadN18)") (class "Default")
      (node (ref "U1") (pin "N18") (pinfunction "PR41C_N18") (pintype "bidirectional"))
    )
    (net (code "197") (name "unconnected-(U1C-PR41D-PadP17)") (class "Default")
      (node (ref "U1") (pin "P17") (pinfunction "PR41D_P17") (pintype "bidirectional"))
    )
    (net (code "198") (name "unconnected-(U1C-PR44A-PadN17)") (class "Default")
      (node (ref "U1") (pin "N17") (pinfunction "PR44A_N17") (pintype "bidirectional"))
    )
    (net (code "199") (name "unconnected-(U1C-PR44B{slash}VREF1_3-PadP16)") (class "Default")
      (node (ref "U1") (pin "P16") (pinfunction "PR44B/VREF1_3_P16") (pintype "bidirectional"))
    )
    (net (code "200") (name "unconnected-(U1C-PR44C-PadR16)") (class "Default")
      (node (ref "U1") (pin "R16") (pinfunction "PR44C_R16") (pintype "bidirectional"))
    )
    (net (code "201") (name "unconnected-(U1C-PR44D-PadR17)") (class "Default")
      (node (ref "U1") (pin "R17") (pinfunction "PR44D_R17") (pintype "bidirectional"))
    )
    (net (code "202") (name "unconnected-(U1C-PR53A-PadT16)") (class "Default")
      (node (ref "U1") (pin "T16") (pinfunction "PR53A_T16") (pintype "bidirectional"))
    )
    (net (code "203") (name "unconnected-(U1C-PR59A-PadN19)") (class "Default")
      (node (ref "U1") (pin "N19") (pinfunction "PR59A_N19") (pintype "bidirectional"))
    )
    (net (code "204") (name "unconnected-(U1C-PR59B-PadN20)") (class "Default")
      (node (ref "U1") (pin "N20") (pinfunction "PR59B_N20") (pintype "bidirectional"))
    )
    (net (code "205") (name "unconnected-(U1C-PR59C-PadP19)") (class "Default")
      (node (ref "U1") (pin "P19") (pinfunction "PR59C_P19") (pintype "bidirectional"))
    )
    (net (code "206") (name "unconnected-(U1C-PR59D-PadP18)") (class "Default")
      (node (ref "U1") (pin "P18") (pinfunction "PR59D_P18") (pintype "bidirectional"))
    )
    (net (code "207") (name "unconnected-(U1C-PR62A-PadP20)") (class "Default")
      (node (ref "U1") (pin "P20") (pinfunction "PR62A_P20") (pintype "bidirectional"))
    )
    (net (code "208") (name "unconnected-(U1C-PR62B-PadR20)") (class "Default")
      (node (ref "U1") (pin "R20") (pinfunction "PR62B_R20") (pintype "bidirectional"))
    )
    (net (code "209") (name "unconnected-(U1C-PR62C-PadT20)") (class "Default")
      (node (ref "U1") (pin "T20") (pinfunction "PR62C_T20") (pintype "bidirectional"))
    )
    (net (code "210") (name "unconnected-(U1C-PR62D-PadU20)") (class "Default")
      (node (ref "U1") (pin "U20") (pinfunction "PR62D_U20") (pintype "bidirectional"))
    )
    (net (code "211") (name "unconnected-(U1C-PR65A-PadT19)") (class "Default")
      (node (ref "U1") (pin "T19") (pinfunction "PR65A_T19") (pintype "bidirectional"))
    )
    (net (code "212") (name "unconnected-(U1C-PR65B-PadR18)") (class "Default")
      (node (ref "U1") (pin "R18") (pinfunction "PR65B_R18") (pintype "bidirectional"))
    )
    (net (code "213") (name "unconnected-(U1C-PR65C-PadU19)") (class "Default")
      (node (ref "U1") (pin "U19") (pinfunction "PR65C_U19") (pintype "bidirectional"))
    )
    (net (code "214") (name "unconnected-(U1C-PR65D-PadT18)") (class "Default")
      (node (ref "U1") (pin "T18") (pinfunction "PR65D_T18") (pintype "bidirectional"))
    )
    (net (code "215") (name "unconnected-(U1C-PR68A-PadU18)") (class "Default")
      (node (ref "U1") (pin "U18") (pinfunction "PR68A_U18") (pintype "bidirectional"))
    )
    (net (code "216") (name "unconnected-(U1C-PR68B-PadU17)") (class "Default")
      (node (ref "U1") (pin "U17") (pinfunction "PR68B_U17") (pintype "bidirectional"))
    )
    (net (code "217") (name "unconnected-(U1C-PR68C{slash}LRC_GPLL0T_IN-PadU16)") (class "Default")
      (node (ref "U1") (pin "U16") (pinfunction "PR68C/LRC_GPLL0T_IN_U16") (pintype "bidirectional"))
    )
    (net (code "218") (name "unconnected-(U1C-PR68D{slash}LRC_GPLL0C_IN-PadT17)") (class "Default")
      (node (ref "U1") (pin "T17") (pinfunction "PR68D/LRC_GPLL0C_IN_T17") (pintype "bidirectional"))
    )
    (net (code "219") (name "unconnected-(U1D-PB4A{slash}D7{slash}IO7-PadR1)") (class "Default")
      (node (ref "U1") (pin "R1") (pinfunction "PB4A/D7/IO7_R1") (pintype "bidirectional"))
    )
    (net (code "220") (name "unconnected-(U1D-PB4B{slash}D6{slash}IO6-PadT1)") (class "Default")
      (node (ref "U1") (pin "T1") (pinfunction "PB4B/D6/IO6_T1") (pintype "bidirectional"))
    )
    (net (code "221") (name "unconnected-(U1D-PB6A{slash}D5{slash}MISO2{slash}IO5-PadU1)") (class "Default")
      (node (ref "U1") (pin "U1") (pinfunction "PB6A/D5/MISO2/IO5_U1") (pintype "bidirectional"))
    )
    (net (code "222") (name "unconnected-(U1D-PB6B{slash}D4{slash}MOSI2{slash}IO4-PadV1)") (class "Default")
      (node (ref "U1") (pin "V1") (pinfunction "PB6B/D4/MOSI2/IO4_V1") (pintype "bidirectional"))
    )
    (net (code "223") (name "unconnected-(U1D-PB9A{slash}D3{slash}IO3-PadW1)") (class "Default")
      (node (ref "U1") (pin "W1") (pinfunction "PB9A/D3/IO3_W1") (pintype "bidirectional"))
    )
    (net (code "224") (name "unconnected-(U1D-PB9B{slash}D2{slash}IO2-PadY2)") (class "Default")
      (node (ref "U1") (pin "Y2") (pinfunction "PB9B/D2/IO2_Y2") (pintype "bidirectional"))
    )
    (net (code "225") (name "unconnected-(U1D-PB13A{slash}SN{slash}CSN-PadT2)") (class "Default")
      (node (ref "U1") (pin "T2") (pinfunction "PB13A/SN/CSN_T2") (pintype "bidirectional"))
    )
    (net (code "226") (name "unconnected-(U1D-PB15A{slash}HOLDN{slash}DI{slash}BUSY{slash}CSSPIN{slash}CEN-PadR2)") (class "Default")
      (node (ref "U1") (pin "R2") (pinfunction "PB15A/HOLDN/DI/BUSY/CSSPIN/CEN_R2") (pintype "bidirectional"))
    )
    (net (code "227") (name "unconnected-(U1D-PB15B{slash}DOUT{slash}CSON-PadR3)") (class "Default")
      (node (ref "U1") (pin "R3") (pinfunction "PB15B/DOUT/CSON_R3") (pintype "bidirectional"))
    )
    (net (code "228") (name "unconnected-(U1D-PB18A{slash}WRITEN-PadT3)") (class "Default")
      (node (ref "U1") (pin "T3") (pinfunction "PB18A/WRITEN_T3") (pintype "bidirectional"))
    )
  )
)
